# PCB_SRCA.net
KiCad netlist of a schematic drawn in EAGLE
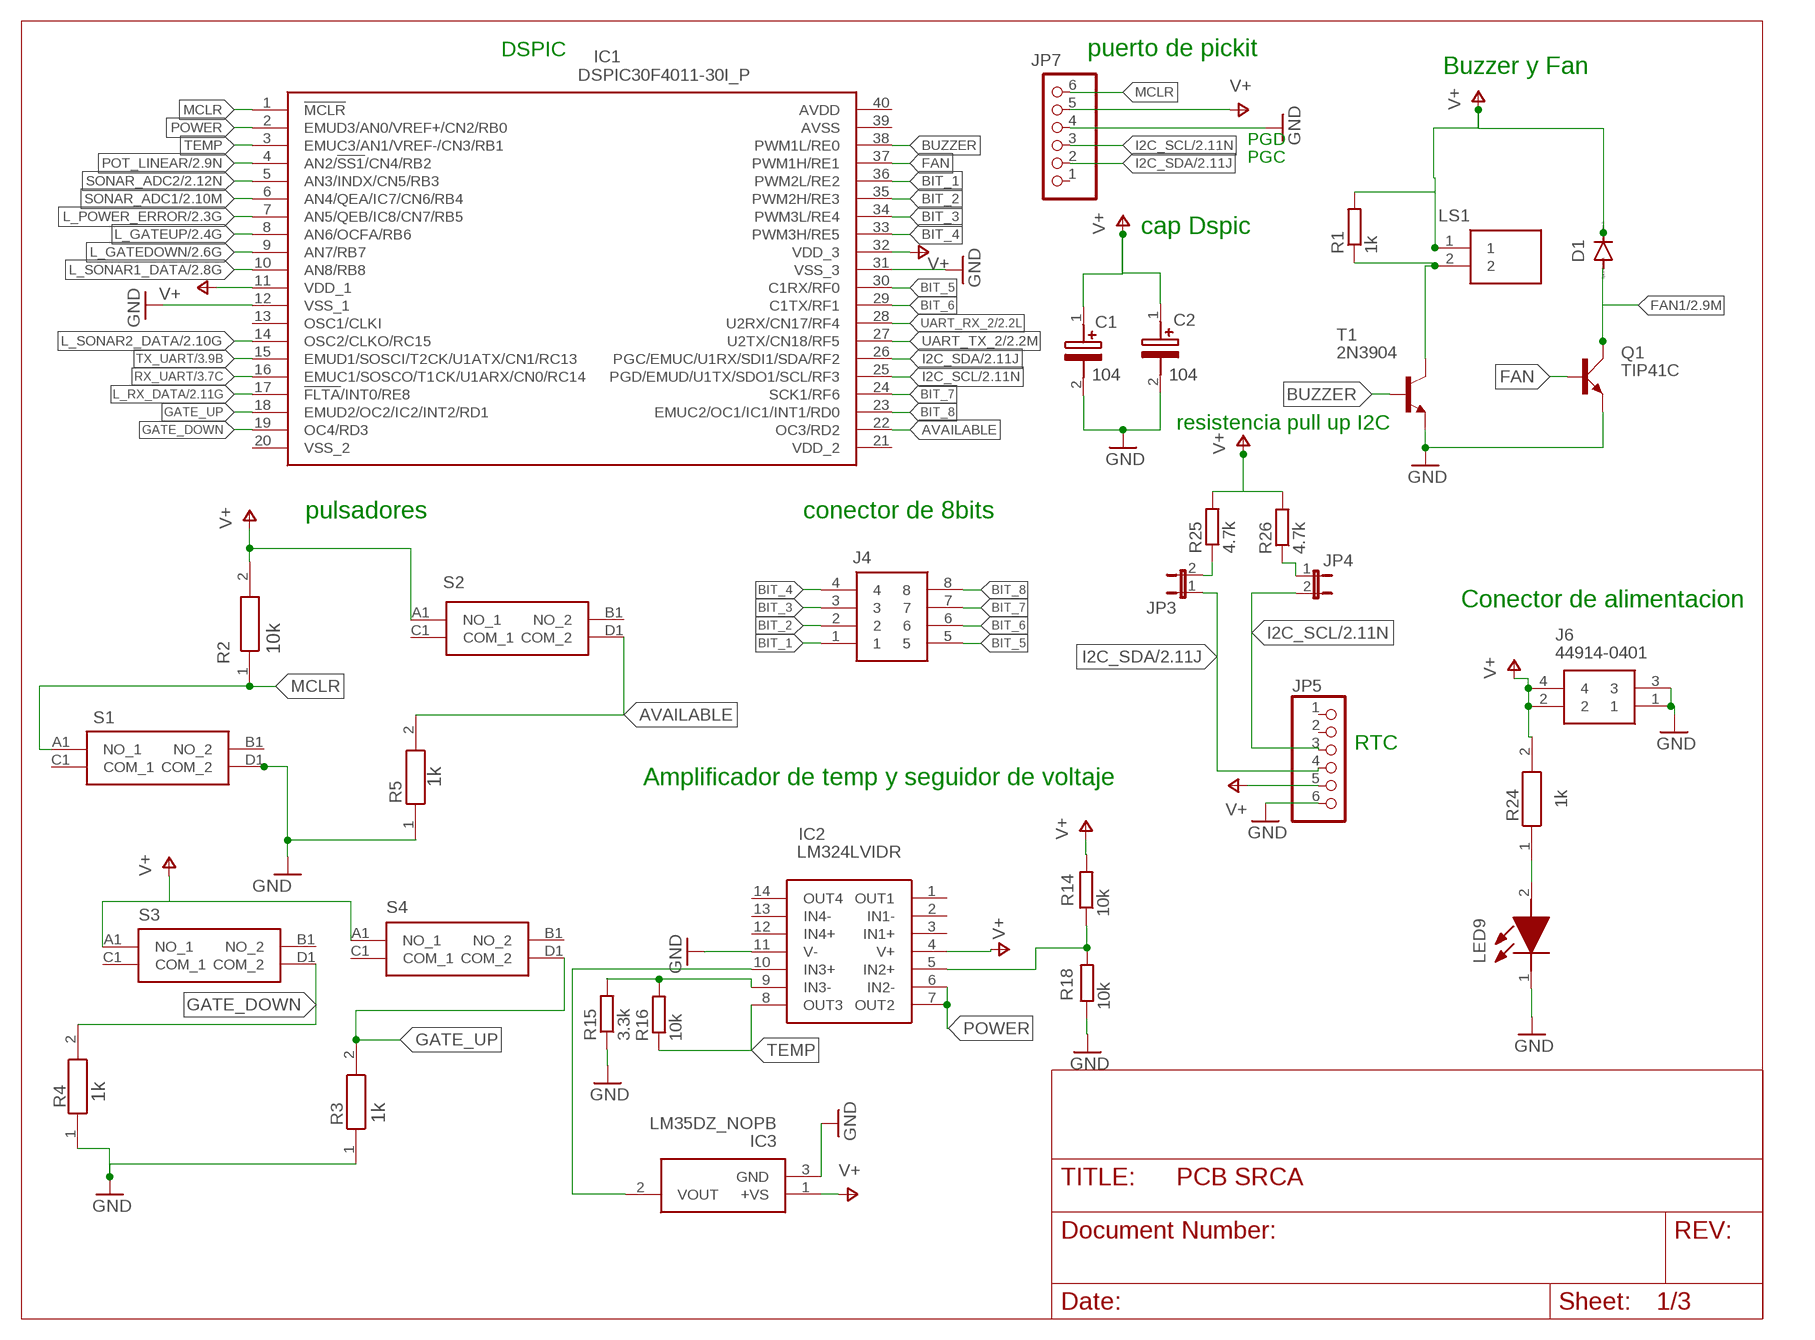
[diagram p0: schematic, sheet 1]
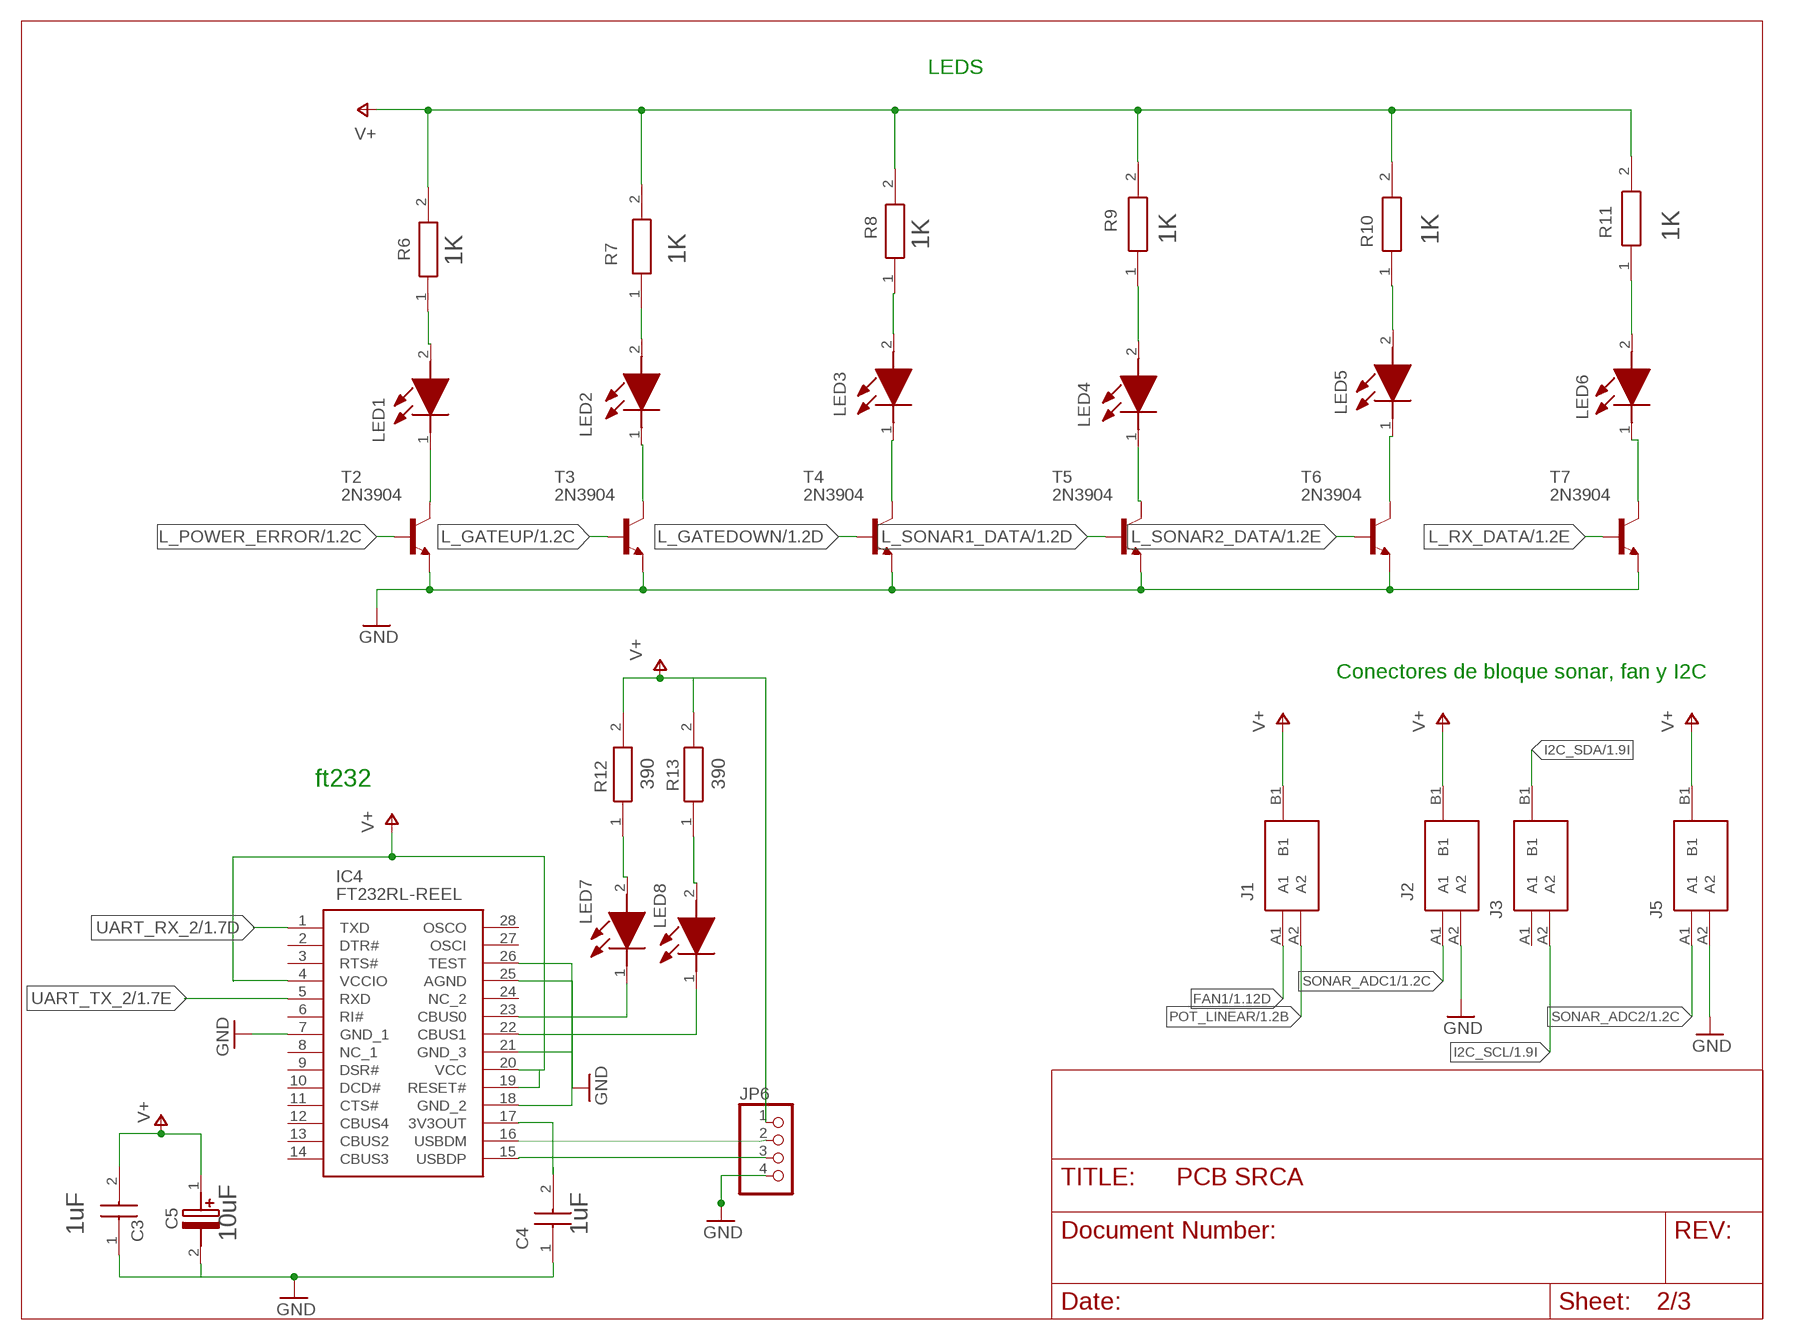
[diagram p1: schematic, sheet 2]
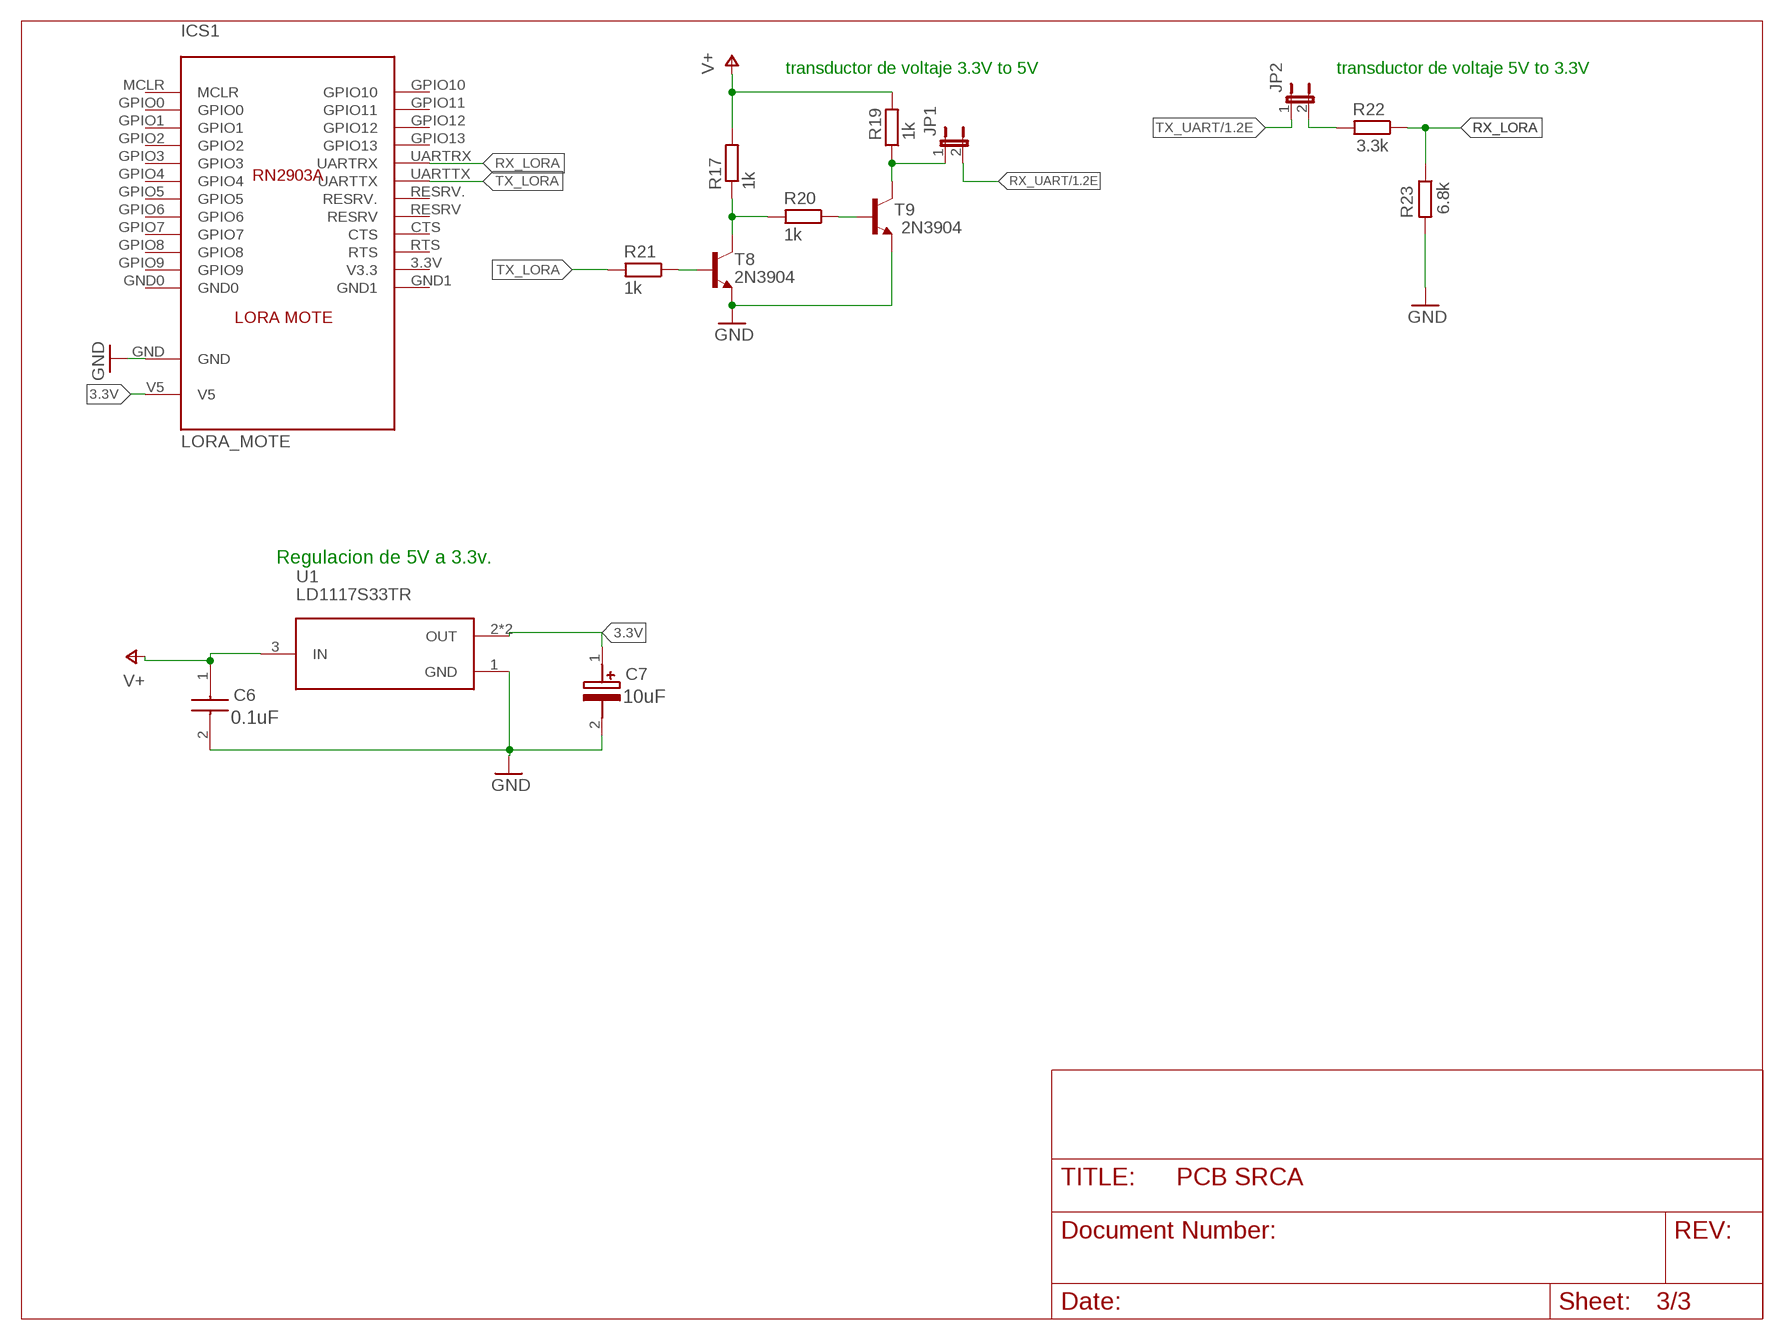
[diagram p2: schematic, sheet 3]

(export (version "E")
  (design (tool "Eeschema 10.0.6"))
  (components
    (comp (ref "C1")
      (value "TAJR104K020RNJ")
      (footprint "eagle-import:CAPPM2014X120N")
      (fields (field (name "MOUSER_PART_NUMBER") "581-TAJR104K020R"))
      (libsource (lib "eagle-import") (part "TAJR104K020RNJ"))
    )
    (comp (ref "C2")
      (value "TAJR104K020RNJ")
      (footprint "eagle-import:CAPPM2014X120N")
      (fields (field (name "MOUSER_PART_NUMBER") "581-TAJR104K020R"))
      (libsource (lib "eagle-import") (part "TAJR104K020RNJ"))
    )
    (comp (ref "D1")
      (value "1N4148DO35-7")
      (footprint "eagle-import:DO35-7")
      (libsource (lib "eagle-import") (part "1N4148DO35-7"))
    )
    (comp (ref "IC1")
      (value "DSPIC30F4011-30I_P")
      (footprint "eagle-import:DIP1543W58P254L5175H635Q40N")
      (fields
        (field (name "ARROW_PART_NUMBER") "dsPIC30F4011-30I/P")
        (field (name "MANUFACTURER_PART_NUMBER") "DSPIC30F4011-30I/P")
        (field (name "MOUSER_PART_NUMBER") "579-30F4011-30I/P")
      )
      (libsource (lib "eagle-import") (part "DSPIC30F4011-30I_P"))
    )
    (comp (ref "IC2")
      (value "LM324LVIDR")
      (footprint "eagle-import:SOIC127P600X175-14N")
      (fields (field (name "MOUSER_PART_NUMBER") "595-LM324LVIDR"))
      (libsource (lib "eagle-import") (part "LM324LVIDR"))
    )
    (comp (ref "IC3")
      (value "LM35DZ_NOPB")
      (footprint "eagle-import:LP0003A")
      (fields
        (field (name "MANUFACTURER_PART_NUMBER") "LM35DZ/NOPB")
        (field (name "MOUSER_PART_NUMBER") "926-LM35DZ/NOPB")
      )
      (libsource (lib "eagle-import") (part "LM35DZ_NOPB"))
    )
    (comp (ref "J4")
      (value "44914-0801")
      (footprint "eagle-import:44914-0801")
      (fields (field (name "MOUSER_PART_NUMBER") "538-44914-0801"))
      (libsource (lib "eagle-import") (part "44914-0801"))
    )
    (comp (ref "J6")
      (value "44914-0401")
      (footprint "eagle-import:44914-0401")
      (fields (field (name "MOUSER_PART_NUMBER") "538-44914-0401"))
      (libsource (lib "eagle-import") (part "44914-0401"))
    )
    (comp (ref "JP3")
      (value "JP1E")
      (footprint "eagle-import:JP1")
      (libsource (lib "eagle-import") (part "JP1E"))
    )
    (comp (ref "JP4")
      (value "JP1E")
      (footprint "eagle-import:JP1")
      (libsource (lib "eagle-import") (part "JP1E"))
    )
    (comp (ref "JP5")
      (value "PINHD-1X6")
      (footprint "eagle-import:1X06")
      (libsource (lib "eagle-import") (part "PINHD-1X6"))
    )
    (comp (ref "JP7")
      (value "PINHD-1X6")
      (footprint "eagle-import:1X06")
      (libsource (lib "eagle-import") (part "PINHD-1X6"))
    )
    (comp (ref "LED9")
      (value "599-0181-007F")
      (footprint "eagle-import:LEDC2012X70N")
      (fields (field (name "MOUSER_PART_NUMBER") "645-599-0181-007F"))
      (libsource (lib "eagle-import") (part "599-0181-007F"))
    )
    (comp (ref "LS1")
      (value "PS1240P02BT")
      (footprint "eagle-import:PS1240P02BT")
      (fields (field (name "MOUSER_PART_NUMBER") "810-PS1240P02BT"))
      (libsource (lib "eagle-import") (part "PS1240P02BT"))
    )
    (comp (ref "Q1")
      (value "TIP41C")
      (footprint "eagle-import:TO220AV")
      (libsource (lib "eagle-import") (part "TIP41C"))
    )
    (comp (ref "R1")
      (value "1k")
      (footprint "eagle-import:0207_10")
      (libsource (lib "eagle-import") (part "R-EU_0207/10"))
    )
    (comp (ref "R2")
      (value "RC0805FR-071KL")
      (footprint "eagle-import:RESC2012X60N")
      (fields (field (name "MOUSER_PART_NUMBER") "603-RC0805FR-071KL"))
      (libsource (lib "eagle-import") (part "RC0805FR-071KL"))
    )
    (comp (ref "R3")
      (value "RC0805FR-071KL")
      (footprint "eagle-import:RESC2012X60N")
      (fields (field (name "MOUSER_PART_NUMBER") "603-RC0805FR-071KL"))
      (libsource (lib "eagle-import") (part "RC0805FR-071KL"))
    )
    (comp (ref "R4")
      (value "RC0805FR-071KL")
      (footprint "eagle-import:RESC2012X60N")
      (fields (field (name "MOUSER_PART_NUMBER") "603-RC0805FR-071KL"))
      (libsource (lib "eagle-import") (part "RC0805FR-071KL"))
    )
    (comp (ref "R5")
      (value "RC0805FR-071KL")
      (footprint "eagle-import:RESC2012X60N")
      (fields (field (name "MOUSER_PART_NUMBER") "603-RC0805FR-071KL"))
      (libsource (lib "eagle-import") (part "RC0805FR-071KL"))
    )
    (comp (ref "R14")
      (value "10k")
      (footprint "eagle-import:0207_10")
      (libsource (lib "eagle-import") (part "R-EU_0207/10"))
    )
    (comp (ref "R15")
      (value "3.3k")
      (footprint "eagle-import:0207_10")
      (libsource (lib "eagle-import") (part "R-EU_0207/10"))
    )
    (comp (ref "R16")
      (value "10k")
      (footprint "eagle-import:0207_10")
      (libsource (lib "eagle-import") (part "R-EU_0207/10"))
    )
    (comp (ref "R18")
      (value "10k")
      (footprint "eagle-import:0207_10")
      (libsource (lib "eagle-import") (part "R-EU_0207/10"))
    )
    (comp (ref "R24")
      (value "RC0805FR-071KL")
      (footprint "eagle-import:RESC2012X60N")
      (fields (field (name "MOUSER_PART_NUMBER") "603-RC0805FR-071KL"))
      (libsource (lib "eagle-import") (part "RC0805FR-071KL"))
    )
    (comp (ref "R25")
      (value "4.7k")
      (footprint "eagle-import:0207_10")
      (libsource (lib "eagle-import") (part "R-EU_0207/10"))
    )
    (comp (ref "R26")
      (value "4.7k")
      (footprint "eagle-import:0207_10")
      (libsource (lib "eagle-import") (part "R-EU_0207/10"))
    )
    (comp (ref "S1")
      (value "PTS645SK50JSMTR92_LFS")
      (footprint "eagle-import:PTS645SK50JSMTR92LFS")
      (fields
        (field (name "MANUFACTURER_PART_NUMBER") "PTS645SK50JSMTR92 LFS")
        (field (name "MOUSER_PART_NUMBER") "611-SK50JSMTR92LFS")
      )
      (libsource (lib "eagle-import") (part "PTS645SK50JSMTR92_LFS"))
    )
    (comp (ref "S2")
      (value "PTS645SK50JSMTR92_LFS")
      (footprint "eagle-import:PTS645SK50JSMTR92LFS")
      (fields
        (field (name "MANUFACTURER_PART_NUMBER") "PTS645SK50JSMTR92 LFS")
        (field (name "MOUSER_PART_NUMBER") "611-SK50JSMTR92LFS")
      )
      (libsource (lib "eagle-import") (part "PTS645SK50JSMTR92_LFS"))
    )
    (comp (ref "S3")
      (value "PTS645SK50JSMTR92_LFS")
      (footprint "eagle-import:PTS645SK50JSMTR92LFS")
      (fields
        (field (name "MANUFACTURER_PART_NUMBER") "PTS645SK50JSMTR92 LFS")
        (field (name "MOUSER_PART_NUMBER") "611-SK50JSMTR92LFS")
      )
      (libsource (lib "eagle-import") (part "PTS645SK50JSMTR92_LFS"))
    )
    (comp (ref "S4")
      (value "PTS645SK50JSMTR92_LFS")
      (footprint "eagle-import:PTS645SK50JSMTR92LFS")
      (fields
        (field (name "MANUFACTURER_PART_NUMBER") "PTS645SK50JSMTR92 LFS")
        (field (name "MOUSER_PART_NUMBER") "611-SK50JSMTR92LFS")
      )
      (libsource (lib "eagle-import") (part "PTS645SK50JSMTR92_LFS"))
    )
    (comp (ref "T1")
      (value "2N3904")
      (footprint "eagle-import:TO92")
      (libsource (lib "eagle-import") (part "2N3904"))
    )
    (comp (ref "C6")
      (value "C0805X104K1RAC3316")
      (footprint "eagle-import:CAPC2012X100N")
      (fields (field (name "MOUSER_PART_NUMBER") "80-C0805X104K1R3316"))
      (libsource (lib "eagle-import") (part "C0805X104K1RAC3316"))
    )
    (comp (ref "C7")
      (value "UUP1C100MCL1GS")
      (footprint "eagle-import:CAPAE530X610N")
      (fields (field (name "MOUSER_PART_NUMBER") "647-UUP1C100MCL1GS"))
      (libsource (lib "eagle-import") (part "UUP1C100MCL1GS"))
    )
    (comp (ref "ICS1")
      (value "LORA_MOTE")
      (footprint "eagle-import:LORA_MOTE_RN2903")
      (libsource (lib "eagle-import") (part "LORA_MOTE"))
    )
    (comp (ref "JP1")
      (value "JP1E")
      (footprint "eagle-import:JP1")
      (libsource (lib "eagle-import") (part "JP1E"))
    )
    (comp (ref "JP2")
      (value "JP1E")
      (footprint "eagle-import:JP1")
      (libsource (lib "eagle-import") (part "JP1E"))
    )
    (comp (ref "R17")
      (value "1k")
      (footprint "eagle-import:0207_10")
      (libsource (lib "eagle-import") (part "R-EU_0207/10"))
    )
    (comp (ref "R19")
      (value "1k")
      (footprint "eagle-import:0207_10")
      (libsource (lib "eagle-import") (part "R-EU_0207/10"))
    )
    (comp (ref "R20")
      (value "1k")
      (footprint "eagle-import:0207_10")
      (libsource (lib "eagle-import") (part "R-EU_0207/10"))
    )
    (comp (ref "R21")
      (value "1k")
      (footprint "eagle-import:0207_10")
      (libsource (lib "eagle-import") (part "R-EU_0207/10"))
    )
    (comp (ref "R22")
      (value "3.3k")
      (footprint "eagle-import:0207_10")
      (libsource (lib "eagle-import") (part "R-EU_0207/10"))
    )
    (comp (ref "R23")
      (value "6.8k")
      (footprint "eagle-import:0207_10")
      (libsource (lib "eagle-import") (part "R-EU_0207/10"))
    )
    (comp (ref "T8")
      (value "2N3904")
      (footprint "eagle-import:TO92")
      (libsource (lib "eagle-import") (part "2N3904"))
    )
    (comp (ref "T9")
      (value "2N3904")
      (footprint "eagle-import:TO92")
      (libsource (lib "eagle-import") (part "2N3904"))
    )
    (comp (ref "U1")
      (value "LD1117S33TR")
      (footprint "eagle-import:SOT230P700X180-4N")
      (fields (field (name "MF") "STMicroelectronics"))
      (libsource (lib "eagle-import") (part "LD1117S33TR"))
    )
    (comp (ref "C3")
      (value "C0805X104K1RAC3316")
      (footprint "eagle-import:CAPC2012X100N")
      (fields (field (name "MOUSER_PART_NUMBER") "80-C0805X104K1R3316"))
      (libsource (lib "eagle-import") (part "C0805X104K1RAC3316"))
    )
    (comp (ref "C4")
      (value "C0805X104K1RAC3316")
      (footprint "eagle-import:CAPC2012X100N")
      (fields (field (name "MOUSER_PART_NUMBER") "80-C0805X104K1R3316"))
      (libsource (lib "eagle-import") (part "C0805X104K1RAC3316"))
    )
    (comp (ref "C5")
      (value "UUP1C100MCL1GS")
      (footprint "eagle-import:CAPAE530X610N")
      (fields (field (name "MOUSER_PART_NUMBER") "647-UUP1C100MCL1GS"))
      (libsource (lib "eagle-import") (part "UUP1C100MCL1GS"))
    )
    (comp (ref "IC4")
      (value "FT232RL-REEL")
      (footprint "eagle-import:SOP65P778X200-28N")
      (fields (field (name "MOUSER_PART_NUMBER") "895-FT232RL"))
      (libsource (lib "eagle-import") (part "FT232RL-REEL"))
    )
    (comp (ref "J1")
      (value "TBL002A-350-03GR-2OR")
      (footprint "eagle-import:TBL002A35003GR2OR")
      (fields (field (name "MOUSER_PART_NUMBER") "490-TBL002A3503GR2OR"))
      (libsource (lib "eagle-import") (part "TBL002A-350-03GR-2OR"))
    )
    (comp (ref "J2")
      (value "TBL002A-350-03GR-2OR")
      (footprint "eagle-import:TBL002A35003GR2OR")
      (fields (field (name "MOUSER_PART_NUMBER") "490-TBL002A3503GR2OR"))
      (libsource (lib "eagle-import") (part "TBL002A-350-03GR-2OR"))
    )
    (comp (ref "J3")
      (value "TBL002A-350-03GR-2OR")
      (footprint "eagle-import:TBL002A35003GR2OR")
      (fields (field (name "MOUSER_PART_NUMBER") "490-TBL002A3503GR2OR"))
      (libsource (lib "eagle-import") (part "TBL002A-350-03GR-2OR"))
    )
    (comp (ref "J5")
      (value "TBL002A-350-03GR-2OR")
      (footprint "eagle-import:TBL002A35003GR2OR")
      (fields (field (name "MOUSER_PART_NUMBER") "490-TBL002A3503GR2OR"))
      (libsource (lib "eagle-import") (part "TBL002A-350-03GR-2OR"))
    )
    (comp (ref "JP6")
      (value "PINHD-1X4")
      (footprint "eagle-import:1X04")
      (libsource (lib "eagle-import") (part "PINHD-1X4"))
    )
    (comp (ref "LED1")
      (value "599-0181-007F")
      (footprint "eagle-import:LEDC2012X70N")
      (fields (field (name "MOUSER_PART_NUMBER") "645-599-0181-007F"))
      (libsource (lib "eagle-import") (part "599-0181-007F"))
    )
    (comp (ref "LED2")
      (value "599-0181-007F")
      (footprint "eagle-import:LEDC2012X70N")
      (fields (field (name "MOUSER_PART_NUMBER") "645-599-0181-007F"))
      (libsource (lib "eagle-import") (part "599-0181-007F"))
    )
    (comp (ref "LED3")
      (value "599-0181-007F")
      (footprint "eagle-import:LEDC2012X70N")
      (fields (field (name "MOUSER_PART_NUMBER") "645-599-0181-007F"))
      (libsource (lib "eagle-import") (part "599-0181-007F"))
    )
    (comp (ref "LED4")
      (value "599-0181-007F")
      (footprint "eagle-import:LEDC2012X70N")
      (fields (field (name "MOUSER_PART_NUMBER") "645-599-0181-007F"))
      (libsource (lib "eagle-import") (part "599-0181-007F"))
    )
    (comp (ref "LED5")
      (value "599-0181-007F")
      (footprint "eagle-import:LEDC2012X70N")
      (fields (field (name "MOUSER_PART_NUMBER") "645-599-0181-007F"))
      (libsource (lib "eagle-import") (part "599-0181-007F"))
    )
    (comp (ref "LED6")
      (value "599-0181-007F")
      (footprint "eagle-import:LEDC2012X70N")
      (fields (field (name "MOUSER_PART_NUMBER") "645-599-0181-007F"))
      (libsource (lib "eagle-import") (part "599-0181-007F"))
    )
    (comp (ref "LED7")
      (value "599-0181-007F")
      (footprint "eagle-import:LEDC2012X70N")
      (fields (field (name "MOUSER_PART_NUMBER") "645-599-0181-007F"))
      (libsource (lib "eagle-import") (part "599-0181-007F"))
    )
    (comp (ref "LED8")
      (value "599-0181-007F")
      (footprint "eagle-import:LEDC2012X70N")
      (fields (field (name "MOUSER_PART_NUMBER") "645-599-0181-007F"))
      (libsource (lib "eagle-import") (part "599-0181-007F"))
    )
    (comp (ref "R6")
      (value "RC0805FR-071KL")
      (footprint "eagle-import:RESC2012X60N")
      (fields (field (name "MOUSER_PART_NUMBER") "603-RC0805FR-071KL"))
      (libsource (lib "eagle-import") (part "RC0805FR-071KL"))
    )
    (comp (ref "R7")
      (value "RC0805FR-071KL")
      (footprint "eagle-import:RESC2012X60N")
      (fields (field (name "MOUSER_PART_NUMBER") "603-RC0805FR-071KL"))
      (libsource (lib "eagle-import") (part "RC0805FR-071KL"))
    )
    (comp (ref "R8")
      (value "RC0805FR-071KL")
      (footprint "eagle-import:RESC2012X60N")
      (fields (field (name "MOUSER_PART_NUMBER") "603-RC0805FR-071KL"))
      (libsource (lib "eagle-import") (part "RC0805FR-071KL"))
    )
    (comp (ref "R9")
      (value "RC0805FR-071KL")
      (footprint "eagle-import:RESC2012X60N")
      (fields (field (name "MOUSER_PART_NUMBER") "603-RC0805FR-071KL"))
      (libsource (lib "eagle-import") (part "RC0805FR-071KL"))
    )
    (comp (ref "R10")
      (value "RC0805FR-071KL")
      (footprint "eagle-import:RESC2012X60N")
      (fields (field (name "MOUSER_PART_NUMBER") "603-RC0805FR-071KL"))
      (libsource (lib "eagle-import") (part "RC0805FR-071KL"))
    )
    (comp (ref "R11")
      (value "RC0805FR-071KL")
      (footprint "eagle-import:RESC2012X60N")
      (fields (field (name "MOUSER_PART_NUMBER") "603-RC0805FR-071KL"))
      (libsource (lib "eagle-import") (part "RC0805FR-071KL"))
    )
    (comp (ref "R12")
      (value "RC0805FR-071KL")
      (footprint "eagle-import:RESC2012X60N")
      (fields (field (name "MOUSER_PART_NUMBER") "603-RC0805FR-071KL"))
      (libsource (lib "eagle-import") (part "RC0805FR-071KL"))
    )
    (comp (ref "R13")
      (value "RC0805FR-071KL")
      (footprint "eagle-import:RESC2012X60N")
      (fields (field (name "MOUSER_PART_NUMBER") "603-RC0805FR-071KL"))
      (libsource (lib "eagle-import") (part "RC0805FR-071KL"))
    )
    (comp (ref "T2")
      (value "2N3904")
      (footprint "eagle-import:TO92")
      (libsource (lib "eagle-import") (part "2N3904"))
    )
    (comp (ref "T3")
      (value "2N3904")
      (footprint "eagle-import:TO92")
      (libsource (lib "eagle-import") (part "2N3904"))
    )
    (comp (ref "T4")
      (value "2N3904")
      (footprint "eagle-import:TO92")
      (libsource (lib "eagle-import") (part "2N3904"))
    )
    (comp (ref "T5")
      (value "2N3904")
      (footprint "eagle-import:TO92")
      (libsource (lib "eagle-import") (part "2N3904"))
    )
    (comp (ref "T6")
      (value "2N3904")
      (footprint "eagle-import:TO92")
      (libsource (lib "eagle-import") (part "2N3904"))
    )
    (comp (ref "T7")
      (value "2N3904")
      (footprint "eagle-import:TO92")
      (libsource (lib "eagle-import") (part "2N3904"))
    )
  )
  (nets
    (net (code "1") (name "3.3V") (class "Default")
      (node (ref "C7") (pin "1") (pinfunction "+_1") (pintype "bidirectional"))
      (node (ref "ICS1") (pin "V5") (pinfunction "V5_V5") (pintype "bidirectional"))
      (node (ref "U1") (pin "2") (pinfunction "OUT_2") (pintype "output"))
      (node (ref "U1") (pin "4") (pinfunction "OUT_4") (pintype "output"))
    )
    (net (code "2") (name "AVAILABLE") (class "Default")
      (node (ref "IC1") (pin "22") (pinfunction "OC3/RD2_22") (pintype "bidirectional"))
      (node (ref "R5") (pin "2") (pinfunction "2_2") (pintype "bidirectional"))
      (node (ref "S2") (pin "D1") (pinfunction "COM_2_D1") (pintype "bidirectional"))
    )
    (net (code "3") (name "BIT_1") (class "Default")
      (node (ref "IC1") (pin "36") (pinfunction "PWM2L/RE2_36") (pintype "bidirectional"))
      (node (ref "J4") (pin "1") (pinfunction "1_1") (pintype "bidirectional"))
    )
    (net (code "4") (name "BIT_2") (class "Default")
      (node (ref "IC1") (pin "35") (pinfunction "PWM2H/RE3_35") (pintype "bidirectional"))
      (node (ref "J4") (pin "2") (pinfunction "2_2") (pintype "bidirectional"))
    )
    (net (code "5") (name "BIT_3") (class "Default")
      (node (ref "IC1") (pin "34") (pinfunction "PWM3L/RE4_34") (pintype "bidirectional"))
      (node (ref "J4") (pin "3") (pinfunction "3_3") (pintype "bidirectional"))
    )
    (net (code "6") (name "BIT_4") (class "Default")
      (node (ref "IC1") (pin "33") (pinfunction "PWM3H/RE5_33") (pintype "bidirectional"))
      (node (ref "J4") (pin "4") (pinfunction "4_4") (pintype "bidirectional"))
    )
    (net (code "7") (name "BIT_5") (class "Default")
      (node (ref "IC1") (pin "30") (pinfunction "C1RX/RF0_30") (pintype "bidirectional"))
      (node (ref "J4") (pin "5") (pinfunction "5_5") (pintype "bidirectional"))
    )
    (net (code "8") (name "BIT_6") (class "Default")
      (node (ref "IC1") (pin "29") (pinfunction "C1TX/RF1_29") (pintype "bidirectional"))
      (node (ref "J4") (pin "6") (pinfunction "6_6") (pintype "bidirectional"))
    )
    (net (code "9") (name "BIT_7") (class "Default")
      (node (ref "IC1") (pin "24") (pinfunction "SCK1/RF6_24") (pintype "bidirectional"))
      (node (ref "J4") (pin "7") (pinfunction "7_7") (pintype "bidirectional"))
    )
    (net (code "10") (name "BIT_8") (class "Default")
      (node (ref "IC1") (pin "23") (pinfunction "EMUC2/OC1/IC1/INT1/RD0_23") (pintype "bidirectional"))
      (node (ref "J4") (pin "8") (pinfunction "8_8") (pintype "bidirectional"))
    )
    (net (code "11") (name "BUZZER") (class "Default")
      (node (ref "IC1") (pin "38") (pinfunction "PWM1L/RE0_38") (pintype "bidirectional"))
      (node (ref "T1") (pin "2") (pinfunction "B_2") (pintype "passive"))
    )
    (net (code "12") (name "FAN") (class "Default")
      (node (ref "IC1") (pin "37") (pinfunction "PWM1H/RE1_37") (pintype "bidirectional"))
      (node (ref "Q1") (pin "B") (pinfunction "B_B") (pintype "passive"))
    )
    (net (code "13") (name "FAN1") (class "Default")
      (node (ref "D1") (pin "A") (pinfunction "A_A") (pintype "passive"))
      (node (ref "J1") (pin "A1") (pinfunction "A1_A1") (pintype "bidirectional"))
      (node (ref "Q1") (pin "C") (pinfunction "C_C") (pintype "passive"))
    )
    (net (code "14") (name "GATE_DOWN") (class "Default")
      (node (ref "IC1") (pin "19") (pinfunction "OC4/RD3_19") (pintype "bidirectional"))
      (node (ref "R4") (pin "2") (pinfunction "2_2") (pintype "bidirectional"))
      (node (ref "S3") (pin "D1") (pinfunction "COM_2_D1") (pintype "bidirectional"))
    )
    (net (code "15") (name "GATE_UP") (class "Default")
      (node (ref "IC1") (pin "18") (pinfunction "EMUD2/OC2/IC2/INT2/RD1_18") (pintype "bidirectional"))
      (node (ref "R3") (pin "2") (pinfunction "2_2") (pintype "bidirectional"))
      (node (ref "S4") (pin "D1") (pinfunction "COM_2_D1") (pintype "bidirectional"))
    )
    (net (code "16") (name "GND") (class "Default")
      (node (ref "C1") (pin "2") (pinfunction "-_2") (pintype "bidirectional"))
      (node (ref "C2") (pin "2") (pinfunction "-_2") (pintype "bidirectional"))
      (node (ref "C3") (pin "1") (pinfunction "1_1") (pintype "bidirectional"))
      (node (ref "C4") (pin "1") (pinfunction "1_1") (pintype "bidirectional"))
      (node (ref "C5") (pin "2") (pinfunction "-_2") (pintype "bidirectional"))
      (node (ref "C6") (pin "2") (pinfunction "2_2") (pintype "bidirectional"))
      (node (ref "C7") (pin "2") (pinfunction "-_2") (pintype "bidirectional"))
      (node (ref "IC1") (pin "12") (pinfunction "VSS_1_12") (pintype "bidirectional"))
      (node (ref "IC1") (pin "31") (pinfunction "VSS_3_31") (pintype "bidirectional"))
      (node (ref "IC2") (pin "11") (pinfunction "V-_11") (pintype "bidirectional"))
      (node (ref "IC3") (pin "3") (pinfunction "GND_3") (pintype "bidirectional"))
      (node (ref "IC4") (pin "18") (pinfunction "GND_2_18") (pintype "bidirectional"))
      (node (ref "IC4") (pin "21") (pinfunction "GND_3_21") (pintype "bidirectional"))
      (node (ref "IC4") (pin "25") (pinfunction "AGND_25") (pintype "bidirectional"))
      (node (ref "IC4") (pin "26") (pinfunction "TEST_26") (pintype "bidirectional"))
      (node (ref "IC4") (pin "7") (pinfunction "GND_1_7") (pintype "bidirectional"))
      (node (ref "ICS1") (pin "GND") (pinfunction "GND_GND") (pintype "bidirectional"))
      (node (ref "J2") (pin "A2") (pinfunction "A2_A2") (pintype "bidirectional"))
      (node (ref "J5") (pin "A2") (pinfunction "A2_A2") (pintype "bidirectional"))
      (node (ref "J6") (pin "1") (pinfunction "1_1") (pintype "bidirectional"))
      (node (ref "J6") (pin "3") (pinfunction "3_3") (pintype "bidirectional"))
      (node (ref "JP5") (pin "6") (pinfunction "6_6") (pintype "passive"))
      (node (ref "JP6") (pin "4") (pinfunction "4_4") (pintype "passive"))
      (node (ref "JP7") (pin "4") (pinfunction "4_4") (pintype "passive"))
      (node (ref "LED9") (pin "1") (pinfunction "K_1") (pintype "bidirectional"))
      (node (ref "Q1") (pin "E") (pinfunction "E_E") (pintype "passive"))
      (node (ref "R15") (pin "1") (pinfunction "1_1") (pintype "passive"))
      (node (ref "R18") (pin "1") (pinfunction "1_1") (pintype "passive"))
      (node (ref "R23") (pin "2") (pinfunction "2_2") (pintype "passive"))
      (node (ref "R3") (pin "1") (pinfunction "1_1") (pintype "bidirectional"))
      (node (ref "R4") (pin "1") (pinfunction "1_1") (pintype "bidirectional"))
      (node (ref "R5") (pin "1") (pinfunction "1_1") (pintype "bidirectional"))
      (node (ref "S1") (pin "D1") (pinfunction "COM_2_D1") (pintype "bidirectional"))
      (node (ref "T1") (pin "3") (pinfunction "E_3") (pintype "passive"))
      (node (ref "T2") (pin "3") (pinfunction "E_3") (pintype "passive"))
      (node (ref "T3") (pin "3") (pinfunction "E_3") (pintype "passive"))
      (node (ref "T4") (pin "3") (pinfunction "E_3") (pintype "passive"))
      (node (ref "T5") (pin "3") (pinfunction "E_3") (pintype "passive"))
      (node (ref "T6") (pin "3") (pinfunction "E_3") (pintype "passive"))
      (node (ref "T7") (pin "3") (pinfunction "E_3") (pintype "passive"))
      (node (ref "T8") (pin "3") (pinfunction "E_3") (pintype "passive"))
      (node (ref "T9") (pin "3") (pinfunction "E_3") (pintype "passive"))
      (node (ref "U1") (pin "1") (pinfunction "GND_1") (pintype "power_in"))
    )
    (net (code "17") (name "I2C_SCL") (class "Default")
      (node (ref "IC1") (pin "25") (pinfunction "PGD/EMUD/U1TX/SDO1/SCL/RF3_25") (pintype "bidirectional"))
      (node (ref "J3") (pin "A2") (pinfunction "A2_A2") (pintype "bidirectional"))
      (node (ref "JP4") (pin "2") (pinfunction "2_2") (pintype "passive"))
      (node (ref "JP5") (pin "3") (pinfunction "3_3") (pintype "passive"))
      (node (ref "JP7") (pin "3") (pinfunction "3_3") (pintype "passive"))
    )
    (net (code "18") (name "I2C_SDA") (class "Default")
      (node (ref "IC1") (pin "26") (pinfunction "PGC/EMUC/U1RX/SDI1/SDA/RF2_26") (pintype "bidirectional"))
      (node (ref "J3") (pin "B1") (pinfunction "B1_B1") (pintype "bidirectional"))
      (node (ref "JP3") (pin "1") (pinfunction "1_1") (pintype "passive"))
      (node (ref "JP5") (pin "4") (pinfunction "4_4") (pintype "passive"))
      (node (ref "JP7") (pin "2") (pinfunction "2_2") (pintype "passive"))
    )
    (net (code "19") (name "L_GATEDOWN") (class "Default")
      (node (ref "IC1") (pin "9") (pinfunction "AN7/RB7_9") (pintype "bidirectional"))
      (node (ref "T4") (pin "2") (pinfunction "B_2") (pintype "passive"))
    )
    (net (code "20") (name "L_GATEUP") (class "Default")
      (node (ref "IC1") (pin "8") (pinfunction "AN6/OCFA/RB6_8") (pintype "bidirectional"))
      (node (ref "T3") (pin "2") (pinfunction "B_2") (pintype "passive"))
    )
    (net (code "21") (name "L_POWER_ERROR") (class "Default")
      (node (ref "IC1") (pin "7") (pinfunction "AN5/QEB/IC8/CN7/RB5_7") (pintype "bidirectional"))
      (node (ref "T2") (pin "2") (pinfunction "B_2") (pintype "passive"))
    )
    (net (code "22") (name "L_RX_DATA") (class "Default")
      (node (ref "IC1") (pin "17") (pinfunction "~{FLTA}/INT0/RE8_17") (pintype "bidirectional"))
      (node (ref "T7") (pin "2") (pinfunction "B_2") (pintype "passive"))
    )
    (net (code "23") (name "L_SONAR1_DATA") (class "Default")
      (node (ref "IC1") (pin "10") (pinfunction "AN8/RB8_10") (pintype "bidirectional"))
      (node (ref "T5") (pin "2") (pinfunction "B_2") (pintype "passive"))
    )
    (net (code "24") (name "L_SONAR2_DATA") (class "Default")
      (node (ref "IC1") (pin "14") (pinfunction "OSC2/CLKO/RC15_14") (pintype "bidirectional"))
      (node (ref "T6") (pin "2") (pinfunction "B_2") (pintype "passive"))
    )
    (net (code "25") (name "MCLR") (class "Default")
      (node (ref "IC1") (pin "1") (pinfunction "~{MCLR}_1") (pintype "bidirectional"))
      (node (ref "JP7") (pin "6") (pinfunction "6_6") (pintype "passive"))
      (node (ref "R2") (pin "1") (pinfunction "1_1") (pintype "bidirectional"))
      (node (ref "S1") (pin "A1") (pinfunction "NO_1_A1") (pintype "bidirectional"))
    )
    (net (code "26") (name "Net-(IC2-IN2+)") (class "Default")
      (node (ref "IC2") (pin "5") (pinfunction "IN2+_5") (pintype "bidirectional"))
      (node (ref "R14") (pin "1") (pinfunction "1_1") (pintype "passive"))
      (node (ref "R18") (pin "2") (pinfunction "2_2") (pintype "passive"))
    )
    (net (code "27") (name "Net-(IC2-IN3+)") (class "Default")
      (node (ref "IC2") (pin "10") (pinfunction "IN3+_10") (pintype "bidirectional"))
      (node (ref "IC3") (pin "2") (pinfunction "VOUT_2") (pintype "bidirectional"))
    )
    (net (code "28") (name "Net-(IC2-IN3-)") (class "Default")
      (node (ref "IC2") (pin "9") (pinfunction "IN3-_9") (pintype "bidirectional"))
      (node (ref "R15") (pin "2") (pinfunction "2_2") (pintype "passive"))
      (node (ref "R16") (pin "2") (pinfunction "2_2") (pintype "passive"))
    )
    (net (code "29") (name "Net-(IC4-3V3OUT)") (class "Default")
      (node (ref "C4") (pin "2") (pinfunction "2_2") (pintype "bidirectional"))
      (node (ref "IC4") (pin "17") (pinfunction "3V3OUT_17") (pintype "bidirectional"))
    )
    (net (code "30") (name "Net-(IC4-CBUS0)") (class "Default")
      (node (ref "IC4") (pin "23") (pinfunction "CBUS0_23") (pintype "bidirectional"))
      (node (ref "LED7") (pin "1") (pinfunction "K_1") (pintype "bidirectional"))
    )
    (net (code "31") (name "Net-(IC4-CBUS1)") (class "Default")
      (node (ref "IC4") (pin "22") (pinfunction "CBUS1_22") (pintype "bidirectional"))
      (node (ref "LED8") (pin "1") (pinfunction "K_1") (pintype "bidirectional"))
    )
    (net (code "32") (name "Net-(IC4-USBDM)") (class "Default")
      (node (ref "IC4") (pin "16") (pinfunction "USBDM_16") (pintype "bidirectional"))
      (node (ref "JP6") (pin "2") (pinfunction "2_2") (pintype "passive"))
    )
    (net (code "33") (name "Net-(IC4-USBDP)") (class "Default")
      (node (ref "IC4") (pin "15") (pinfunction "USBDP_15") (pintype "bidirectional"))
      (node (ref "JP6") (pin "3") (pinfunction "3_3") (pintype "passive"))
    )
    (net (code "34") (name "Net-(JP2-Pad2)") (class "Default")
      (node (ref "JP2") (pin "2") (pinfunction "2_2") (pintype "passive"))
      (node (ref "R22") (pin "2") (pinfunction "2_2") (pintype "passive"))
    )
    (net (code "35") (name "Net-(JP3-Pad2)") (class "Default")
      (node (ref "JP3") (pin "2") (pinfunction "2_2") (pintype "passive"))
      (node (ref "R25") (pin "1") (pinfunction "1_1") (pintype "passive"))
    )
    (net (code "36") (name "Net-(JP4-Pad1)") (class "Default")
      (node (ref "JP4") (pin "1") (pinfunction "1_1") (pintype "passive"))
      (node (ref "R26") (pin "1") (pinfunction "1_1") (pintype "passive"))
    )
    (net (code "37") (name "Net-(LED1-A)") (class "Default")
      (node (ref "LED1") (pin "2") (pinfunction "A_2") (pintype "bidirectional"))
      (node (ref "R6") (pin "1") (pinfunction "1_1") (pintype "bidirectional"))
    )
    (net (code "38") (name "Net-(LED1-K)") (class "Default")
      (node (ref "LED1") (pin "1") (pinfunction "K_1") (pintype "bidirectional"))
      (node (ref "T2") (pin "1") (pinfunction "C_1") (pintype "passive"))
    )
    (net (code "39") (name "Net-(LED2-A)") (class "Default")
      (node (ref "LED2") (pin "2") (pinfunction "A_2") (pintype "bidirectional"))
      (node (ref "R7") (pin "1") (pinfunction "1_1") (pintype "bidirectional"))
    )
    (net (code "40") (name "Net-(LED2-K)") (class "Default")
      (node (ref "LED2") (pin "1") (pinfunction "K_1") (pintype "bidirectional"))
      (node (ref "T3") (pin "1") (pinfunction "C_1") (pintype "passive"))
    )
    (net (code "41") (name "Net-(LED3-A)") (class "Default")
      (node (ref "LED3") (pin "2") (pinfunction "A_2") (pintype "bidirectional"))
      (node (ref "R8") (pin "1") (pinfunction "1_1") (pintype "bidirectional"))
    )
    (net (code "42") (name "Net-(LED3-K)") (class "Default")
      (node (ref "LED3") (pin "1") (pinfunction "K_1") (pintype "bidirectional"))
      (node (ref "T4") (pin "1") (pinfunction "C_1") (pintype "passive"))
    )
    (net (code "43") (name "Net-(LED4-A)") (class "Default")
      (node (ref "LED4") (pin "2") (pinfunction "A_2") (pintype "bidirectional"))
      (node (ref "R9") (pin "1") (pinfunction "1_1") (pintype "bidirectional"))
    )
    (net (code "44") (name "Net-(LED4-K)") (class "Default")
      (node (ref "LED4") (pin "1") (pinfunction "K_1") (pintype "bidirectional"))
      (node (ref "T5") (pin "1") (pinfunction "C_1") (pintype "passive"))
    )
    (net (code "45") (name "Net-(LED5-A)") (class "Default")
      (node (ref "LED5") (pin "2") (pinfunction "A_2") (pintype "bidirectional"))
      (node (ref "R10") (pin "1") (pinfunction "1_1") (pintype "bidirectional"))
    )
    (net (code "46") (name "Net-(LED5-K)") (class "Default")
      (node (ref "LED5") (pin "1") (pinfunction "K_1") (pintype "bidirectional"))
      (node (ref "T6") (pin "1") (pinfunction "C_1") (pintype "passive"))
    )
    (net (code "47") (name "Net-(LED6-A)") (class "Default")
      (node (ref "LED6") (pin "2") (pinfunction "A_2") (pintype "bidirectional"))
      (node (ref "R11") (pin "1") (pinfunction "1_1") (pintype "bidirectional"))
    )
    (net (code "48") (name "Net-(LED6-K)") (class "Default")
      (node (ref "LED6") (pin "1") (pinfunction "K_1") (pintype "bidirectional"))
      (node (ref "T7") (pin "1") (pinfunction "C_1") (pintype "passive"))
    )
    (net (code "49") (name "Net-(LED7-A)") (class "Default")
      (node (ref "LED7") (pin "2") (pinfunction "A_2") (pintype "bidirectional"))
      (node (ref "R12") (pin "1") (pinfunction "1_1") (pintype "bidirectional"))
    )
    (net (code "50") (name "Net-(LED8-A)") (class "Default")
      (node (ref "LED8") (pin "2") (pinfunction "A_2") (pintype "bidirectional"))
      (node (ref "R13") (pin "1") (pinfunction "1_1") (pintype "bidirectional"))
    )
    (net (code "51") (name "Net-(LED9-A)") (class "Default")
      (node (ref "LED9") (pin "2") (pinfunction "A_2") (pintype "bidirectional"))
      (node (ref "R24") (pin "1") (pinfunction "1_1") (pintype "bidirectional"))
    )
    (net (code "52") (name "Net-(T1-C)") (class "Default")
      (node (ref "LS1") (pin "2") (pinfunction "2_2") (pintype "bidirectional"))
      (node (ref "R1") (pin "1") (pinfunction "1_1") (pintype "passive"))
      (node (ref "T1") (pin "1") (pinfunction "C_1") (pintype "passive"))
    )
    (net (code "53") (name "Net-(T8-B)") (class "Default")
      (node (ref "R21") (pin "1") (pinfunction "1_1") (pintype "passive"))
      (node (ref "T8") (pin "2") (pinfunction "B_2") (pintype "passive"))
    )
    (net (code "54") (name "Net-(T8-C)") (class "Default")
      (node (ref "R17") (pin "1") (pinfunction "1_1") (pintype "passive"))
      (node (ref "R20") (pin "2") (pinfunction "2_2") (pintype "passive"))
      (node (ref "T8") (pin "1") (pinfunction "C_1") (pintype "passive"))
    )
    (net (code "55") (name "Net-(T9-B)") (class "Default")
      (node (ref "R20") (pin "1") (pinfunction "1_1") (pintype "passive"))
      (node (ref "T9") (pin "2") (pinfunction "B_2") (pintype "passive"))
    )
    (net (code "56") (name "Net-(T9-C)") (class "Default")
      (node (ref "JP1") (pin "1") (pinfunction "1_1") (pintype "passive"))
      (node (ref "R19") (pin "1") (pinfunction "1_1") (pintype "passive"))
      (node (ref "T9") (pin "1") (pinfunction "C_1") (pintype "passive"))
    )
    (net (code "57") (name "POT_LINEAR") (class "Default")
      (node (ref "IC1") (pin "4") (pinfunction "AN2/~{SS1}/CN4/RB2_4") (pintype "bidirectional"))
      (node (ref "J1") (pin "A2") (pinfunction "A2_A2") (pintype "bidirectional"))
    )
    (net (code "58") (name "POWER") (class "Default")
      (node (ref "IC1") (pin "2") (pinfunction "EMUD3/AN0/VREF+/CN2/RB0_2") (pintype "bidirectional"))
      (node (ref "IC2") (pin "6") (pinfunction "IN2-_6") (pintype "bidirectional"))
      (node (ref "IC2") (pin "7") (pinfunction "OUT2_7") (pintype "bidirectional"))
    )
    (net (code "59") (name "RX_LORA") (class "Default")
      (node (ref "ICS1") (pin "UARTRX") (pinfunction "UARTRX_UARTRX") (pintype "bidirectional"))
      (node (ref "R22") (pin "1") (pinfunction "1_1") (pintype "passive"))
      (node (ref "R23") (pin "1") (pinfunction "1_1") (pintype "passive"))
    )
    (net (code "60") (name "RX_UART") (class "Default")
      (node (ref "IC1") (pin "16") (pinfunction "EMUC1/SOSCO/T1CK/U1ARX/CN0/RC14_16") (pintype "bidirectional"))
      (node (ref "JP1") (pin "2") (pinfunction "2_2") (pintype "passive"))
    )
    (net (code "61") (name "SONAR_ADC1") (class "Default")
      (node (ref "IC1") (pin "6") (pinfunction "AN4/QEA/IC7/CN6/RB4_6") (pintype "bidirectional"))
      (node (ref "J2") (pin "A1") (pinfunction "A1_A1") (pintype "bidirectional"))
    )
    (net (code "62") (name "SONAR_ADC2") (class "Default")
      (node (ref "IC1") (pin "5") (pinfunction "AN3/INDX/CN5/RB3_5") (pintype "bidirectional"))
      (node (ref "J5") (pin "A1") (pinfunction "A1_A1") (pintype "bidirectional"))
    )
    (net (code "63") (name "TEMP") (class "Default")
      (node (ref "IC1") (pin "3") (pinfunction "EMUC3/AN1/VREF-/CN3/RB1_3") (pintype "bidirectional"))
      (node (ref "IC2") (pin "8") (pinfunction "OUT3_8") (pintype "bidirectional"))
      (node (ref "R16") (pin "1") (pinfunction "1_1") (pintype "passive"))
    )
    (net (code "64") (name "TX_LORA") (class "Default")
      (node (ref "ICS1") (pin "UARTTX") (pinfunction "UARTTX_UARTTX") (pintype "bidirectional"))
      (node (ref "R21") (pin "2") (pinfunction "2_2") (pintype "passive"))
    )
    (net (code "65") (name "TX_UART") (class "Default")
      (node (ref "IC1") (pin "15") (pinfunction "EMUD1/SOSCI/T2CK/U1ATX/CN1/RC13_15") (pintype "bidirectional"))
      (node (ref "JP2") (pin "1") (pinfunction "1_1") (pintype "passive"))
    )
    (net (code "66") (name "UART_RX_2") (class "Default")
      (node (ref "IC1") (pin "28") (pinfunction "U2RX/CN17/RF4_28") (pintype "bidirectional"))
      (node (ref "IC4") (pin "1") (pinfunction "TXD_1") (pintype "bidirectional"))
    )
    (net (code "67") (name "UART_TX_2") (class "Default")
      (node (ref "IC1") (pin "27") (pinfunction "U2TX/CN18/RF5_27") (pintype "bidirectional"))
      (node (ref "IC4") (pin "5") (pinfunction "RXD_5") (pintype "bidirectional"))
    )
    (net (code "68") (name "V+") (class "Default")
      (node (ref "C1") (pin "1") (pinfunction "+_1") (pintype "bidirectional"))
      (node (ref "C2") (pin "1") (pinfunction "+_1") (pintype "bidirectional"))
      (node (ref "C3") (pin "2") (pinfunction "2_2") (pintype "bidirectional"))
      (node (ref "C5") (pin "1") (pinfunction "+_1") (pintype "bidirectional"))
      (node (ref "C6") (pin "1") (pinfunction "1_1") (pintype "bidirectional"))
      (node (ref "D1") (pin "C") (pinfunction "C_C") (pintype "passive"))
      (node (ref "IC1") (pin "11") (pinfunction "VDD_1_11") (pintype "bidirectional"))
      (node (ref "IC1") (pin "32") (pinfunction "VDD_3_32") (pintype "bidirectional"))
      (node (ref "IC2") (pin "4") (pinfunction "V+_4") (pintype "bidirectional"))
      (node (ref "IC3") (pin "1") (pinfunction "+VS_1") (pintype "bidirectional"))
      (node (ref "IC4") (pin "19") (pinfunction "RESET#_19") (pintype "bidirectional"))
      (node (ref "IC4") (pin "20") (pinfunction "VCC_20") (pintype "bidirectional"))
      (node (ref "IC4") (pin "4") (pinfunction "VCCIO_4") (pintype "bidirectional"))
      (node (ref "J1") (pin "B1") (pinfunction "B1_B1") (pintype "bidirectional"))
      (node (ref "J2") (pin "B1") (pinfunction "B1_B1") (pintype "bidirectional"))
      (node (ref "J5") (pin "B1") (pinfunction "B1_B1") (pintype "bidirectional"))
      (node (ref "J6") (pin "2") (pinfunction "2_2") (pintype "bidirectional"))
      (node (ref "J6") (pin "4") (pinfunction "4_4") (pintype "bidirectional"))
      (node (ref "JP5") (pin "5") (pinfunction "5_5") (pintype "passive"))
      (node (ref "JP6") (pin "1") (pinfunction "1_1") (pintype "passive"))
      (node (ref "JP7") (pin "5") (pinfunction "5_5") (pintype "passive"))
      (node (ref "LS1") (pin "1") (pinfunction "1_1") (pintype "bidirectional"))
      (node (ref "R1") (pin "2") (pinfunction "2_2") (pintype "passive"))
      (node (ref "R10") (pin "2") (pinfunction "2_2") (pintype "bidirectional"))
      (node (ref "R11") (pin "2") (pinfunction "2_2") (pintype "bidirectional"))
      (node (ref "R12") (pin "2") (pinfunction "2_2") (pintype "bidirectional"))
      (node (ref "R13") (pin "2") (pinfunction "2_2") (pintype "bidirectional"))
      (node (ref "R14") (pin "2") (pinfunction "2_2") (pintype "passive"))
      (node (ref "R17") (pin "2") (pinfunction "2_2") (pintype "passive"))
      (node (ref "R19") (pin "2") (pinfunction "2_2") (pintype "passive"))
      (node (ref "R2") (pin "2") (pinfunction "2_2") (pintype "bidirectional"))
      (node (ref "R24") (pin "2") (pinfunction "2_2") (pintype "bidirectional"))
      (node (ref "R25") (pin "2") (pinfunction "2_2") (pintype "passive"))
      (node (ref "R26") (pin "2") (pinfunction "2_2") (pintype "passive"))
      (node (ref "R6") (pin "2") (pinfunction "2_2") (pintype "bidirectional"))
      (node (ref "R7") (pin "2") (pinfunction "2_2") (pintype "bidirectional"))
      (node (ref "R8") (pin "2") (pinfunction "2_2") (pintype "bidirectional"))
      (node (ref "R9") (pin "2") (pinfunction "2_2") (pintype "bidirectional"))
      (node (ref "S2") (pin "A1") (pinfunction "NO_1_A1") (pintype "bidirectional"))
      (node (ref "S3") (pin "A1") (pinfunction "NO_1_A1") (pintype "bidirectional"))
      (node (ref "S4") (pin "A1") (pinfunction "NO_1_A1") (pintype "bidirectional"))
      (node (ref "U1") (pin "3") (pinfunction "IN_3") (pintype "input"))
    )
    (net (code "69") (name "unconnected-(IC1-AVDD-Pad40)") (class "Default")
      (node (ref "IC1") (pin "40") (pinfunction "AVDD_40") (pintype "bidirectional"))
    )
    (net (code "70") (name "unconnected-(IC1-AVSS-Pad39)") (class "Default")
      (node (ref "IC1") (pin "39") (pinfunction "AVSS_39") (pintype "bidirectional"))
    )
    (net (code "71") (name "unconnected-(IC1-OSC1{slash}CLKI-Pad13)") (class "Default")
      (node (ref "IC1") (pin "13") (pinfunction "OSC1/CLKI_13") (pintype "bidirectional"))
    )
    (net (code "72") (name "unconnected-(IC1-VDD_2-Pad21)") (class "Default")
      (node (ref "IC1") (pin "21") (pinfunction "VDD_2_21") (pintype "bidirectional"))
    )
    (net (code "73") (name "unconnected-(IC1-VSS_2-Pad20)") (class "Default")
      (node (ref "IC1") (pin "20") (pinfunction "VSS_2_20") (pintype "bidirectional"))
    )
    (net (code "74") (name "unconnected-(IC2-IN1+-Pad3)") (class "Default")
      (node (ref "IC2") (pin "3") (pinfunction "IN1+_3") (pintype "bidirectional"))
    )
    (net (code "75") (name "unconnected-(IC2-IN1--Pad2)") (class "Default")
      (node (ref "IC2") (pin "2") (pinfunction "IN1-_2") (pintype "bidirectional"))
    )
    (net (code "76") (name "unconnected-(IC2-IN4+-Pad12)") (class "Default")
      (node (ref "IC2") (pin "12") (pinfunction "IN4+_12") (pintype "bidirectional"))
    )
    (net (code "77") (name "unconnected-(IC2-IN4--Pad13)") (class "Default")
      (node (ref "IC2") (pin "13") (pinfunction "IN4-_13") (pintype "bidirectional"))
    )
    (net (code "78") (name "unconnected-(IC2-OUT1-Pad1)") (class "Default")
      (node (ref "IC2") (pin "1") (pinfunction "OUT1_1") (pintype "bidirectional"))
    )
    (net (code "79") (name "unconnected-(IC2-OUT4-Pad14)") (class "Default")
      (node (ref "IC2") (pin "14") (pinfunction "OUT4_14") (pintype "bidirectional"))
    )
    (net (code "80") (name "unconnected-(IC4-CBUS2-Pad13)") (class "Default")
      (node (ref "IC4") (pin "13") (pinfunction "CBUS2_13") (pintype "bidirectional"))
    )
    (net (code "81") (name "unconnected-(IC4-CBUS3-Pad14)") (class "Default")
      (node (ref "IC4") (pin "14") (pinfunction "CBUS3_14") (pintype "bidirectional"))
    )
    (net (code "82") (name "unconnected-(IC4-CBUS4-Pad12)") (class "Default")
      (node (ref "IC4") (pin "12") (pinfunction "CBUS4_12") (pintype "bidirectional"))
    )
    (net (code "83") (name "unconnected-(IC4-CTS#-Pad11)") (class "Default")
      (node (ref "IC4") (pin "11") (pinfunction "CTS#_11") (pintype "bidirectional"))
    )
    (net (code "84") (name "unconnected-(IC4-DCD#-Pad10)") (class "Default")
      (node (ref "IC4") (pin "10") (pinfunction "DCD#_10") (pintype "bidirectional"))
    )
    (net (code "85") (name "unconnected-(IC4-DSR#-Pad9)") (class "Default")
      (node (ref "IC4") (pin "9") (pinfunction "DSR#_9") (pintype "bidirectional"))
    )
    (net (code "86") (name "unconnected-(IC4-DTR#-Pad2)") (class "Default")
      (node (ref "IC4") (pin "2") (pinfunction "DTR#_2") (pintype "bidirectional"))
    )
    (net (code "87") (name "unconnected-(IC4-NC_1-Pad8)") (class "Default")
      (node (ref "IC4") (pin "8") (pinfunction "NC_1_8") (pintype "bidirectional"))
    )
    (net (code "88") (name "unconnected-(IC4-NC_2-Pad24)") (class "Default")
      (node (ref "IC4") (pin "24") (pinfunction "NC_2_24") (pintype "bidirectional"))
    )
    (net (code "89") (name "unconnected-(IC4-OSCI-Pad27)") (class "Default")
      (node (ref "IC4") (pin "27") (pinfunction "OSCI_27") (pintype "bidirectional"))
    )
    (net (code "90") (name "unconnected-(IC4-OSCO-Pad28)") (class "Default")
      (node (ref "IC4") (pin "28") (pinfunction "OSCO_28") (pintype "bidirectional"))
    )
    (net (code "91") (name "unconnected-(IC4-RI#-Pad6)") (class "Default")
      (node (ref "IC4") (pin "6") (pinfunction "RI#_6") (pintype "bidirectional"))
    )
    (net (code "92") (name "unconnected-(IC4-RTS#-Pad3)") (class "Default")
      (node (ref "IC4") (pin "3") (pinfunction "RTS#_3") (pintype "bidirectional"))
    )
    (net (code "93") (name "unconnected-(ICS1-PadCTS)") (class "Default")
      (node (ref "ICS1") (pin "CTS") (pinfunction "CTS_CTS") (pintype "bidirectional"))
    )
    (net (code "94") (name "unconnected-(ICS1-PadGND0)") (class "Default")
      (node (ref "ICS1") (pin "GND0") (pinfunction "GND0_GND0") (pintype "bidirectional"))
    )
    (net (code "95") (name "unconnected-(ICS1-PadGND1)") (class "Default")
      (node (ref "ICS1") (pin "GND1") (pinfunction "GND1_GND1") (pintype "bidirectional"))
    )
    (net (code "96") (name "unconnected-(ICS1-PadGPIO0)") (class "Default")
      (node (ref "ICS1") (pin "GPIO0") (pinfunction "GPIO0_GPIO0") (pintype "bidirectional"))
    )
    (net (code "97") (name "unconnected-(ICS1-PadGPIO1)") (class "Default")
      (node (ref "ICS1") (pin "GPIO1") (pinfunction "GPIO1_GPIO1") (pintype "bidirectional"))
    )
    (net (code "98") (name "unconnected-(ICS1-PadGPIO2)") (class "Default")
      (node (ref "ICS1") (pin "GPIO2") (pinfunction "GPIO2_GPIO2") (pintype "bidirectional"))
    )
    (net (code "99") (name "unconnected-(ICS1-PadGPIO3)") (class "Default")
      (node (ref "ICS1") (pin "GPIO3") (pinfunction "GPIO3_GPIO3") (pintype "bidirectional"))
    )
    (net (code "100") (name "unconnected-(ICS1-PadGPIO4)") (class "Default")
      (node (ref "ICS1") (pin "GPIO4") (pinfunction "GPIO4_GPIO4") (pintype "bidirectional"))
    )
    (net (code "101") (name "unconnected-(ICS1-PadGPIO5)") (class "Default")
      (node (ref "ICS1") (pin "GPIO5") (pinfunction "GPIO5_GPIO5") (pintype "bidirectional"))
    )
    (net (code "102") (name "unconnected-(ICS1-PadGPIO6)") (class "Default")
      (node (ref "ICS1") (pin "GPIO6") (pinfunction "GPIO6_GPIO6") (pintype "bidirectional"))
    )
    (net (code "103") (name "unconnected-(ICS1-PadGPIO7)") (class "Default")
      (node (ref "ICS1") (pin "GPIO7") (pinfunction "GPIO7_GPIO7") (pintype "bidirectional"))
    )
    (net (code "104") (name "unconnected-(ICS1-PadGPIO8)") (class "Default")
      (node (ref "ICS1") (pin "GPIO8") (pinfunction "GPIO8_GPIO8") (pintype "bidirectional"))
    )
    (net (code "105") (name "unconnected-(ICS1-PadGPIO9)") (class "Default")
      (node (ref "ICS1") (pin "GPIO9") (pinfunction "GPIO9_GPIO9") (pintype "bidirectional"))
    )
    (net (code "106") (name "unconnected-(ICS1-PadGPIO10)") (class "Default")
      (node (ref "ICS1") (pin "GPIO10") (pinfunction "GPIO10_GPIO10") (pintype "bidirectional"))
    )
    (net (code "107") (name "unconnected-(ICS1-PadGPIO11)") (class "Default")
      (node (ref "ICS1") (pin "GPIO11") (pinfunction "GPIO11_GPIO11") (pintype "bidirectional"))
    )
    (net (code "108") (name "unconnected-(ICS1-PadGPIO12)") (class "Default")
      (node (ref "ICS1") (pin "GPIO12") (pinfunction "GPIO12_GPIO12") (pintype "bidirectional"))
    )
    (net (code "109") (name "unconnected-(ICS1-PadGPIO13)") (class "Default")
      (node (ref "ICS1") (pin "GPIO13") (pinfunction "GPIO13_GPIO13") (pintype "bidirectional"))
    )
    (net (code "110") (name "unconnected-(ICS1-PadMCLR)") (class "Default")
      (node (ref "ICS1") (pin "MCLR") (pinfunction "MCLR_MCLR") (pintype "bidirectional"))
    )
    (net (code "111") (name "unconnected-(ICS1-PadRESRV)") (class "Default")
      (node (ref "ICS1") (pin "RESRV") (pinfunction "RESRV_RESRV") (pintype "bidirectional"))
    )
    (net (code "112") (name "unconnected-(ICS1-PadRESRV.)") (class "Default")
      (node (ref "ICS1") (pin "RESRV.") (pinfunction "RESRV._RESRV.") (pintype "bidirectional"))
    )
    (net (code "113") (name "unconnected-(ICS1-PadRTS)") (class "Default")
      (node (ref "ICS1") (pin "RTS") (pinfunction "RTS_RTS") (pintype "bidirectional"))
    )
    (net (code "114") (name "unconnected-(ICS1-V3.3-Pad3.3V)") (class "Default")
      (node (ref "ICS1") (pin "3.3V") (pinfunction "V3.3_3.3V") (pintype "bidirectional"))
    )
    (net (code "115") (name "unconnected-(J3-PadA1)") (class "Default")
      (node (ref "J3") (pin "A1") (pinfunction "A1_A1") (pintype "bidirectional"))
    )
    (net (code "116") (name "unconnected-(JP5-Pad1)") (class "Default")
      (node (ref "JP5") (pin "1") (pinfunction "1_1") (pintype "passive"))
    )
    (net (code "117") (name "unconnected-(JP5-Pad2)") (class "Default")
      (node (ref "JP5") (pin "2") (pinfunction "2_2") (pintype "passive"))
    )
    (net (code "118") (name "unconnected-(JP7-Pad1)") (class "Default")
      (node (ref "JP7") (pin "1") (pinfunction "1_1") (pintype "passive"))
    )
    (net (code "119") (name "unconnected-(S1-COM_1-PadC1)") (class "Default")
      (node (ref "S1") (pin "C1") (pinfunction "COM_1_C1") (pintype "bidirectional"))
    )
    (net (code "120") (name "unconnected-(S1-NO_2-PadB1)") (class "Default")
      (node (ref "S1") (pin "B1") (pinfunction "NO_2_B1") (pintype "bidirectional"))
    )
    (net (code "121") (name "unconnected-(S2-COM_1-PadC1)") (class "Default")
      (node (ref "S2") (pin "C1") (pinfunction "COM_1_C1") (pintype "bidirectional"))
    )
    (net (code "122") (name "unconnected-(S2-NO_2-PadB1)") (class "Default")
      (node (ref "S2") (pin "B1") (pinfunction "NO_2_B1") (pintype "bidirectional"))
    )
    (net (code "123") (name "unconnected-(S3-COM_1-PadC1)") (class "Default")
      (node (ref "S3") (pin "C1") (pinfunction "COM_1_C1") (pintype "bidirectional"))
    )
    (net (code "124") (name "unconnected-(S3-NO_2-PadB1)") (class "Default")
      (node (ref "S3") (pin "B1") (pinfunction "NO_2_B1") (pintype "bidirectional"))
    )
    (net (code "125") (name "unconnected-(S4-COM_1-PadC1)") (class "Default")
      (node (ref "S4") (pin "C1") (pinfunction "COM_1_C1") (pintype "bidirectional"))
    )
    (net (code "126") (name "unconnected-(S4-NO_2-PadB1)") (class "Default")
      (node (ref "S4") (pin "B1") (pinfunction "NO_2_B1") (pintype "bidirectional"))
    )
  )
)
